# CPU.net
KiCad netlist of a schematic drawn in Altium Designer
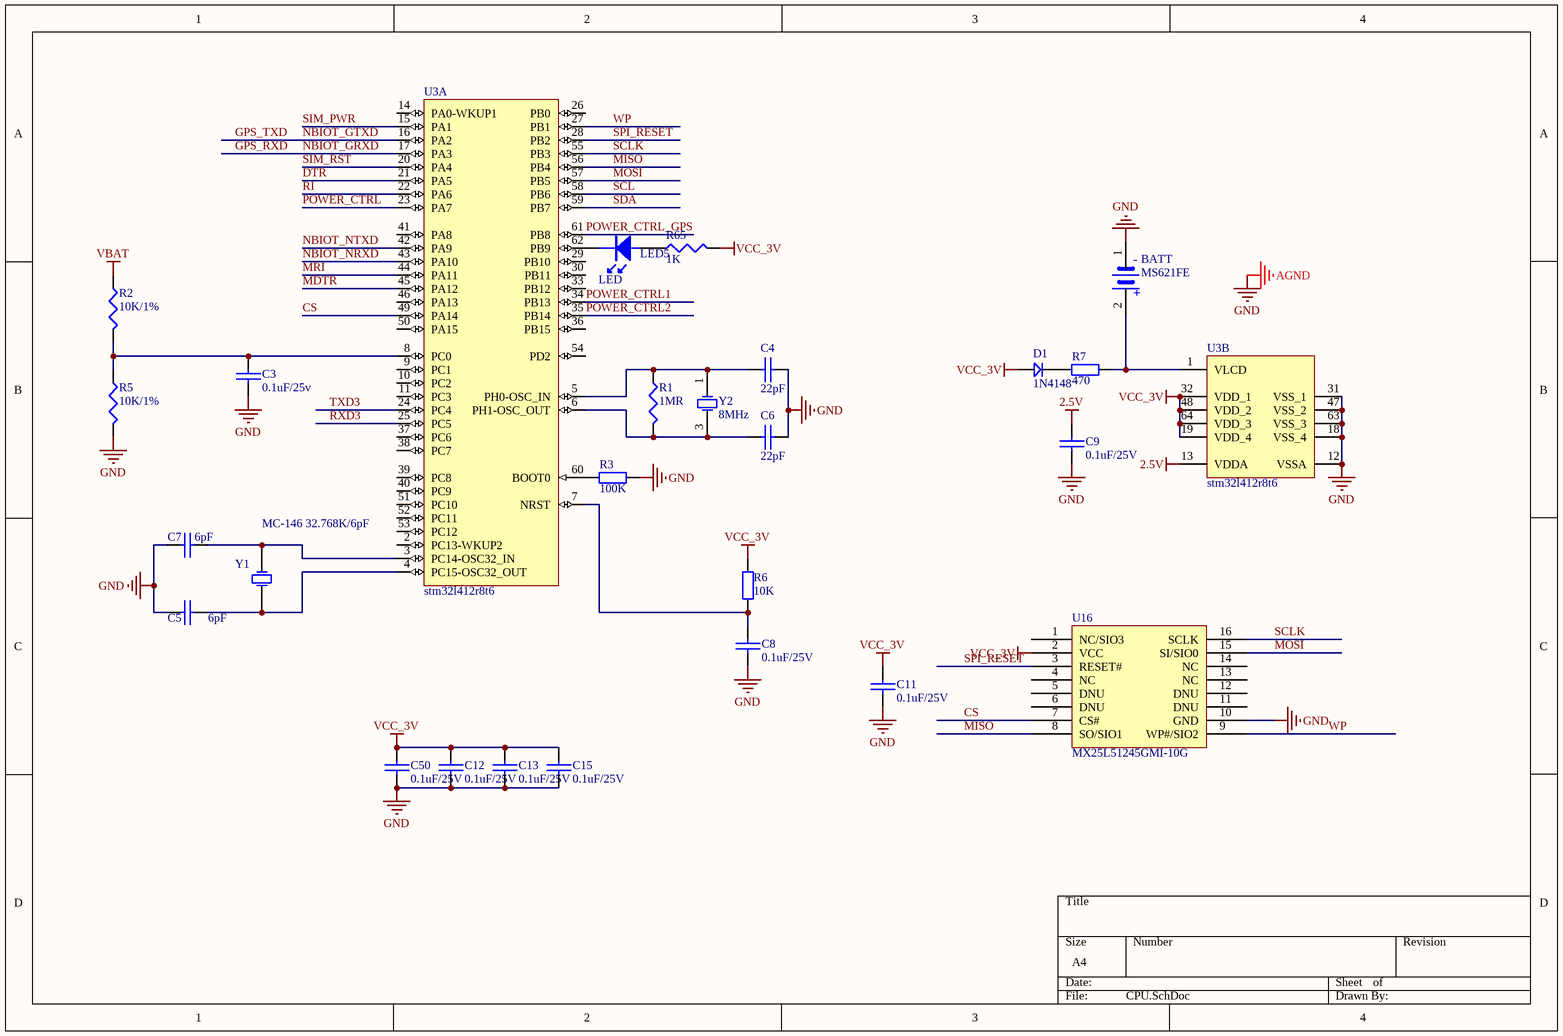
[diagram p0: CPU.SchDoc]

(export (version "E")
  (design (tool "Eeschema 10.0.6"))
  (components
    (comp (ref "BATT") (value "MS621FE") (footprint "MS621FE") (libsource (lib "Myself_1") (part "SBatery")))
    (comp (ref "C3")
      (value "0.1uF/25v")
      (footprint "0402c")
      (description "Capacitor")
      (libsource (lib "SM") (part "CAP"))
    )
    (comp (ref "C4")
      (value "22pF")
      (footprint "0402c")
      (description "Capacitor")
      (libsource (lib "SM") (part "CAP"))
    )
    (comp (ref "C5")
      (value "6pF")
      (footprint "0402c")
      (description "Capacitor")
      (libsource (lib "SM") (part "CAP"))
    )
    (comp (ref "C6")
      (value "22pF")
      (footprint "0402c")
      (description "Capacitor")
      (libsource (lib "SM") (part "CAP"))
    )
    (comp (ref "C7")
      (value "6pF")
      (footprint "0402c")
      (description "Capacitor")
      (libsource (lib "SM") (part "CAP"))
    )
    (comp (ref "C8")
      (value "0.1uF/25V")
      (footprint "0402C")
      (description "Capacitor")
      (libsource (lib "ZWLIntegrated_Library") (part "CAP"))
    )
    (comp (ref "C9")
      (value "0.1uF/25V")
      (footprint "0402C")
      (description "Capacitor")
      (libsource (lib "ZWLIntegrated_Library") (part "CAP"))
    )
    (comp (ref "C11")
      (value "0.1uF/25V")
      (footprint "0402C")
      (description "Capacitor")
      (libsource (lib "ZWLIntegrated_Library") (part "CAP"))
    )
    (comp (ref "C12")
      (value "0.1uF/25V")
      (footprint "0402C")
      (description "Capacitor")
      (libsource (lib "ZWLIntegrated_Library") (part "CAP"))
    )
    (comp (ref "C13")
      (value "0.1uF/25V")
      (footprint "0402C")
      (description "Capacitor")
      (libsource (lib "ZWLIntegrated_Library") (part "CAP"))
    )
    (comp (ref "C15")
      (value "0.1uF/25V")
      (footprint "0402C")
      (description "Capacitor")
      (libsource (lib "ZWLIntegrated_Library") (part "CAP"))
    )
    (comp (ref "C50")
      (value "0.1uF/25V")
      (footprint "0402C")
      (description "Capacitor")
      (libsource (lib "ZWLIntegrated_Library") (part "CAP"))
    )
    (comp (ref "D1")
      (value "1N4148")
      (footprint "DIODE_SOP")
      (libsource (lib "Explorer STM32F407封装库") (part "D"))
    )
    (comp (ref "LED5") (value "LED") (footprint "0603LED") (libsource (lib "我的元件库") (part "LED")))
    (comp (ref "R1")
      (value "1MR")
      (footprint "0402R")
      (description "Resistor")
      (fields (field (name "PUBLISHER") "Altium Limited"))
      (libsource (lib "SM") (part "Res3"))
    )
    (comp (ref "R2")
      (value "10K/1%")
      (footprint "0402R")
      (libsource (lib "ZWLIntegrated_Library") (part "RES1"))
    )
    (comp (ref "R3")
      (value "100K")
      (footprint "0402R")
      (description "Resistor")
      (fields (field (name "PUBLISHER") "Altium Limited"))
      (libsource (lib "Miscellaneous Devices") (part "Res2"))
    )
    (comp (ref "R5")
      (value "10K/1%")
      (footprint "0402R")
      (libsource (lib "ZWLIntegrated_Library") (part "RES1"))
    )
    (comp (ref "R6")
      (value "10K")
      (footprint "0402R")
      (description "Resistor")
      (fields (field (name "PUBLISHER") "Altium Limited"))
      (libsource (lib "") (part "Res2_1"))
    )
    (comp (ref "R7")
      (value "470")
      (footprint "0402R")
      (description "Resistor")
      (fields (field (name "PUBLISHER") "Altium Limited"))
      (libsource (lib "Miscellaneous Devices") (part "Res2"))
    )
    (comp (ref "R65")
      (value "1K")
      (footprint "0402R")
      (libsource (lib "ZWLIntegrated_Library") (part "RES1"))
    )
    (comp (ref "U3")
      (value "stm32l412r8t6")
      (footprint "LQFP-64")
      (fields (field (name "MANUFACTURER") "STMicroelectronics") (field (name "PARTNUMBER") "STM32L100R8T6"))
      (libsource (lib "STMicroelectronics STM32 L1") (part "STM32L100R8T6"))
    )
    (comp (ref "U16")
      (value "MX25L51245GMI-10G")
      (footprint "SOP127P1030X239-16N")
      (libsource (lib "stm32") (part "MX25L51245GMI-10G"))
    )
    (comp (ref "Y1")
      (value "MC-146 32.768K/6pF")
      (footprint "32.768K")
      (description "Crystal Oscillator")
      (fields (field (name "PUBLISHER") "Altium Limited"))
      (libsource (lib "") (part "XTAL_1"))
    )
    (comp (ref "Y2")
      (value "8MHz")
      (footprint "OSCILLATOR-3.2X2.5")
      (description "Crystal Oscillator")
      (fields (field (name "PUBLISHER") "Altium Limited"))
      (libsource (lib "Miscellaneous Devices") (part "XTAL"))
    )
  )
  (nets
    (net (code "1") (name "/CS") (class "Default")
      (node (ref "U16") (pin "7") (pinfunction "CS#_7") (pintype "passive"))
      (node (ref "U3") (pin "49") (pinfunction "PA14_49") (pintype "bidirectional"))
    )
    (net (code "2") (name "/DTR") (class "Default")
      (node (ref "U3") (pin "21") (pinfunction "PA5_21") (pintype "bidirectional"))
    )
    (net (code "3") (name "/GPS_RXD") (class "Default")
      (node (ref "U3") (pin "17") (pinfunction "PA3_17") (pintype "bidirectional"))
    )
    (net (code "4") (name "/GPS_TXD") (class "Default")
      (node (ref "U3") (pin "16") (pinfunction "PA2_16") (pintype "bidirectional"))
    )
    (net (code "5") (name "/MDTR") (class "Default")
      (node (ref "U3") (pin "45") (pinfunction "PA12_45") (pintype "bidirectional"))
    )
    (net (code "6") (name "/MISO") (class "Default")
      (node (ref "U16") (pin "8") (pinfunction "SO/SIO1_8") (pintype "passive"))
      (node (ref "U3") (pin "56") (pinfunction "PB4_56") (pintype "bidirectional"))
    )
    (net (code "7") (name "/MOSI") (class "Default")
      (node (ref "U16") (pin "15") (pinfunction "SI/SIO0_15") (pintype "passive"))
      (node (ref "U3") (pin "57") (pinfunction "PB5_57") (pintype "bidirectional"))
    )
    (net (code "8") (name "/MRI") (class "Default")
      (node (ref "U3") (pin "44") (pinfunction "PA11_44") (pintype "bidirectional"))
    )
    (net (code "9") (name "/NBIOT_NRXD") (class "Default")
      (node (ref "U3") (pin "43") (pinfunction "PA10_43") (pintype "bidirectional"))
    )
    (net (code "10") (name "/NBIOT_NTXD") (class "Default")
      (node (ref "U3") (pin "42") (pinfunction "PA9_42") (pintype "bidirectional"))
    )
    (net (code "11") (name "/POWER_CTRL") (class "Default")
      (node (ref "U3") (pin "23") (pinfunction "PA7_23") (pintype "bidirectional"))
    )
    (net (code "12") (name "/POWER_CTRL1") (class "Default")
      (node (ref "U3") (pin "34") (pinfunction "PB13_34") (pintype "bidirectional"))
    )
    (net (code "13") (name "/POWER_CTRL2") (class "Default")
      (node (ref "U3") (pin "35") (pinfunction "PB14_35") (pintype "bidirectional"))
    )
    (net (code "14") (name "/POWER_CTRL_GPS") (class "Default")
      (node (ref "U3") (pin "61") (pinfunction "PB8_61") (pintype "bidirectional"))
    )
    (net (code "15") (name "/RI") (class "Default")
      (node (ref "U3") (pin "22") (pinfunction "PA6_22") (pintype "bidirectional"))
    )
    (net (code "16") (name "/RXD3") (class "Default")
      (node (ref "U3") (pin "25") (pinfunction "PC5_25") (pintype "bidirectional"))
    )
    (net (code "17") (name "/SCL") (class "Default")
      (node (ref "U3") (pin "58") (pinfunction "PB6_58") (pintype "bidirectional"))
    )
    (net (code "18") (name "/SCLK") (class "Default")
      (node (ref "U16") (pin "16") (pinfunction "SCLK_16") (pintype "passive"))
      (node (ref "U3") (pin "55") (pinfunction "PB3_55") (pintype "bidirectional"))
    )
    (net (code "19") (name "/SDA") (class "Default")
      (node (ref "U3") (pin "59") (pinfunction "PB7_59") (pintype "bidirectional"))
    )
    (net (code "20") (name "/SIM_PWR") (class "Default")
      (node (ref "U3") (pin "15") (pinfunction "PA1_15") (pintype "bidirectional"))
    )
    (net (code "21") (name "/SIM_RST") (class "Default")
      (node (ref "U3") (pin "20") (pinfunction "PA4_20") (pintype "bidirectional"))
    )
    (net (code "22") (name "/SPI_RESET") (class "Default")
      (node (ref "U16") (pin "3") (pinfunction "RESET#_3") (pintype "passive"))
      (node (ref "U3") (pin "28") (pinfunction "PB2_28") (pintype "bidirectional"))
    )
    (net (code "23") (name "/TXD3") (class "Default")
      (node (ref "U3") (pin "24") (pinfunction "PC4_24") (pintype "bidirectional"))
    )
    (net (code "24") (name "/WP") (class "Default")
      (node (ref "U16") (pin "9") (pinfunction "WP#/SIO2_9") (pintype "passive"))
      (node (ref "U3") (pin "27") (pinfunction "PB1_27") (pintype "bidirectional"))
    )
    (net (code "25") (name "2.5V") (class "Default")
      (node (ref "C9") (pin "2") (pinfunction "2_2") (pintype "passive"))
      (node (ref "U3") (pin "13") (pinfunction "VDDA_13") (pintype "power_in"))
    )
    (net (code "26") (name "AGND") (class "Default")
      (node (ref "BATT") (pin "1") (pinfunction "1_1") (pintype "passive"))
      (node (ref "C11") (pin "1") (pinfunction "1_1") (pintype "passive"))
      (node (ref "C12") (pin "1") (pinfunction "1_1") (pintype "passive"))
      (node (ref "C13") (pin "1") (pinfunction "1_1") (pintype "passive"))
      (node (ref "C15") (pin "1") (pinfunction "1_1") (pintype "passive"))
      (node (ref "C3") (pin "2") (pinfunction "2_2") (pintype "passive"))
      (node (ref "C4") (pin "1") (pinfunction "1_1") (pintype "passive"))
      (node (ref "C5") (pin "2") (pinfunction "2_2") (pintype "passive"))
      (node (ref "C50") (pin "1") (pinfunction "1_1") (pintype "passive"))
      (node (ref "C6") (pin "1") (pinfunction "1_1") (pintype "passive"))
      (node (ref "C7") (pin "2") (pinfunction "2_2") (pintype "passive"))
      (node (ref "C8") (pin "1") (pinfunction "1_1") (pintype "passive"))
      (node (ref "C9") (pin "1") (pinfunction "1_1") (pintype "passive"))
      (node (ref "R3") (pin "2") (pinfunction "2_2") (pintype "passive"))
      (node (ref "R5") (pin "2") (pinfunction "2_2") (pintype "passive"))
      (node (ref "U16") (pin "10") (pinfunction "GND_10") (pintype "passive"))
      (node (ref "U3") (pin "12") (pinfunction "VSSA_12") (pintype "power_in"))
      (node (ref "U3") (pin "18") (pinfunction "VSS_4_18") (pintype "power_in"))
      (node (ref "U3") (pin "31") (pinfunction "VSS_1_31") (pintype "power_in"))
      (node (ref "U3") (pin "47") (pinfunction "VSS_2_47") (pintype "power_in"))
      (node (ref "U3") (pin "63") (pinfunction "VSS_3_63") (pintype "power_in"))
    )
    (net (code "27") (name "Net-(D1-Pad2)") (class "Default")
      (node (ref "D1") (pin "2") (pintype "passive"))
      (node (ref "R7") (pin "1") (pinfunction "1_1") (pintype "passive"))
    )
    (net (code "28") (name "Net-(LED5-Pad1)") (class "Default")
      (node (ref "LED5") (pin "1") (pinfunction "1_1") (pintype "passive"))
      (node (ref "R65") (pin "1") (pinfunction "1_1") (pintype "passive"))
    )
    (net (code "29") (name "Net-(U3A-BOOT0)") (class "Default")
      (node (ref "R3") (pin "1") (pinfunction "1_1") (pintype "passive"))
      (node (ref "U3") (pin "60") (pinfunction "BOOT0_60") (pintype "input"))
    )
    (net (code "30") (name "Net-(U3A-NRST)") (class "Default")
      (node (ref "C8") (pin "2") (pinfunction "2_2") (pintype "passive"))
      (node (ref "R6") (pin "2") (pinfunction "2_2") (pintype "passive"))
      (node (ref "U3") (pin "7") (pinfunction "NRST_7") (pintype "bidirectional"))
    )
    (net (code "31") (name "Net-(U3A-PB9)") (class "Default")
      (node (ref "LED5") (pin "2") (pinfunction "2_2") (pintype "passive"))
      (node (ref "U3") (pin "62") (pinfunction "PB9_62") (pintype "bidirectional"))
    )
    (net (code "32") (name "Net-(U3A-PC0)") (class "Default")
      (node (ref "C3") (pin "1") (pinfunction "1_1") (pintype "passive"))
      (node (ref "R2") (pin "2") (pinfunction "2_2") (pintype "passive"))
      (node (ref "R5") (pin "1") (pinfunction "1_1") (pintype "passive"))
      (node (ref "U3") (pin "8") (pinfunction "PC0_8") (pintype "bidirectional"))
    )
    (net (code "33") (name "Net-(U3A-PC14-OSC32_IN)") (class "Default")
      (node (ref "C7") (pin "1") (pinfunction "1_1") (pintype "passive"))
      (node (ref "U3") (pin "3") (pinfunction "PC14-OSC32_IN_3") (pintype "bidirectional"))
      (node (ref "Y1") (pin "1") (pinfunction "OSC1_1") (pintype "passive"))
    )
    (net (code "34") (name "Net-(U3A-PC15-OSC32_OUT)") (class "Default")
      (node (ref "C5") (pin "1") (pinfunction "1_1") (pintype "passive"))
      (node (ref "U3") (pin "4") (pinfunction "PC15-OSC32_OUT_4") (pintype "bidirectional"))
      (node (ref "Y1") (pin "2") (pinfunction "OSC2_2") (pintype "passive"))
    )
    (net (code "35") (name "Net-(U3A-PH0-OSC_IN)") (class "Default")
      (node (ref "C4") (pin "2") (pinfunction "2_2") (pintype "passive"))
      (node (ref "R1") (pin "1") (pinfunction "1_1") (pintype "passive"))
      (node (ref "U3") (pin "5") (pinfunction "PH0-OSC_IN_5") (pintype "bidirectional"))
      (node (ref "Y2") (pin "1") (pinfunction "OSC1_1") (pintype "passive"))
    )
    (net (code "36") (name "Net-(U3A-PH1-OSC_OUT)") (class "Default")
      (node (ref "C6") (pin "2") (pinfunction "2_2") (pintype "passive"))
      (node (ref "R1") (pin "2") (pinfunction "2_2") (pintype "passive"))
      (node (ref "U3") (pin "6") (pinfunction "PH1-OSC_OUT_6") (pintype "bidirectional"))
      (node (ref "Y2") (pin "3") (pinfunction "OSC2_3") (pintype "passive"))
    )
    (net (code "37") (name "Net-(U3B-VLCD)") (class "Default")
      (node (ref "BATT") (pin "2") (pinfunction "2_2") (pintype "passive"))
      (node (ref "R7") (pin "2") (pinfunction "2_2") (pintype "passive"))
      (node (ref "U3") (pin "1") (pinfunction "VLCD_1") (pintype "power_in"))
    )
    (net (code "38") (name "VBAT") (class "Default")
      (node (ref "R2") (pin "1") (pinfunction "1_1") (pintype "passive"))
    )
    (net (code "39") (name "VCC_3V") (class "Default")
      (node (ref "C11") (pin "2") (pinfunction "2_2") (pintype "passive"))
      (node (ref "C12") (pin "2") (pinfunction "2_2") (pintype "passive"))
      (node (ref "C13") (pin "2") (pinfunction "2_2") (pintype "passive"))
      (node (ref "C15") (pin "2") (pinfunction "2_2") (pintype "passive"))
      (node (ref "C50") (pin "2") (pinfunction "2_2") (pintype "passive"))
      (node (ref "D1") (pin "1") (pintype "passive"))
      (node (ref "R6") (pin "1") (pinfunction "1_1") (pintype "passive"))
      (node (ref "R65") (pin "2") (pinfunction "2_2") (pintype "passive"))
      (node (ref "U16") (pin "2") (pinfunction "VCC_2") (pintype "passive"))
      (node (ref "U3") (pin "19") (pinfunction "VDD_4_19") (pintype "power_in"))
      (node (ref "U3") (pin "32") (pinfunction "VDD_1_32") (pintype "power_in"))
      (node (ref "U3") (pin "48") (pinfunction "VDD_2_48") (pintype "power_in"))
      (node (ref "U3") (pin "64") (pinfunction "VDD_3_64") (pintype "power_in"))
    )
    (net (code "40") (name "unconnected-(U3A-PA0-WKUP1-Pad14)") (class "Default")
      (node (ref "U3") (pin "14") (pinfunction "PA0-WKUP1_14") (pintype "bidirectional"))
    )
    (net (code "41") (name "unconnected-(U3A-PA8-Pad41)") (class "Default")
      (node (ref "U3") (pin "41") (pinfunction "PA8_41") (pintype "bidirectional"))
    )
    (net (code "42") (name "unconnected-(U3A-PA13-Pad46)") (class "Default")
      (node (ref "U3") (pin "46") (pinfunction "PA13_46") (pintype "bidirectional"))
    )
    (net (code "43") (name "unconnected-(U3A-PA15-Pad50)") (class "Default")
      (node (ref "U3") (pin "50") (pinfunction "PA15_50") (pintype "bidirectional"))
    )
    (net (code "44") (name "unconnected-(U3A-PB0-Pad26)") (class "Default")
      (node (ref "U3") (pin "26") (pinfunction "PB0_26") (pintype "bidirectional"))
    )
    (net (code "45") (name "unconnected-(U3A-PB10-Pad29)") (class "Default")
      (node (ref "U3") (pin "29") (pinfunction "PB10_29") (pintype "bidirectional"))
    )
    (net (code "46") (name "unconnected-(U3A-PB11-Pad30)") (class "Default")
      (node (ref "U3") (pin "30") (pinfunction "PB11_30") (pintype "bidirectional"))
    )
    (net (code "47") (name "unconnected-(U3A-PB12-Pad33)") (class "Default")
      (node (ref "U3") (pin "33") (pinfunction "PB12_33") (pintype "bidirectional"))
    )
    (net (code "48") (name "unconnected-(U3A-PB15-Pad36)") (class "Default")
      (node (ref "U3") (pin "36") (pinfunction "PB15_36") (pintype "bidirectional"))
    )
    (net (code "49") (name "unconnected-(U3A-PC1-Pad9)") (class "Default")
      (node (ref "U3") (pin "9") (pinfunction "PC1_9") (pintype "bidirectional"))
    )
    (net (code "50") (name "unconnected-(U3A-PC2-Pad10)") (class "Default")
      (node (ref "U3") (pin "10") (pinfunction "PC2_10") (pintype "bidirectional"))
    )
    (net (code "51") (name "unconnected-(U3A-PC3-Pad11)") (class "Default")
      (node (ref "U3") (pin "11") (pinfunction "PC3_11") (pintype "bidirectional"))
    )
    (net (code "52") (name "unconnected-(U3A-PC6-Pad37)") (class "Default")
      (node (ref "U3") (pin "37") (pinfunction "PC6_37") (pintype "bidirectional"))
    )
    (net (code "53") (name "unconnected-(U3A-PC7-Pad38)") (class "Default")
      (node (ref "U3") (pin "38") (pinfunction "PC7_38") (pintype "bidirectional"))
    )
    (net (code "54") (name "unconnected-(U3A-PC8-Pad39)") (class "Default")
      (node (ref "U3") (pin "39") (pinfunction "PC8_39") (pintype "bidirectional"))
    )
    (net (code "55") (name "unconnected-(U3A-PC9-Pad40)") (class "Default")
      (node (ref "U3") (pin "40") (pinfunction "PC9_40") (pintype "bidirectional"))
    )
    (net (code "56") (name "unconnected-(U3A-PC10-Pad51)") (class "Default")
      (node (ref "U3") (pin "51") (pinfunction "PC10_51") (pintype "bidirectional"))
    )
    (net (code "57") (name "unconnected-(U3A-PC11-Pad52)") (class "Default")
      (node (ref "U3") (pin "52") (pinfunction "PC11_52") (pintype "bidirectional"))
    )
    (net (code "58") (name "unconnected-(U3A-PC12-Pad53)") (class "Default")
      (node (ref "U3") (pin "53") (pinfunction "PC12_53") (pintype "bidirectional"))
    )
    (net (code "59") (name "unconnected-(U3A-PC13-WKUP2-Pad2)") (class "Default")
      (node (ref "U3") (pin "2") (pinfunction "PC13-WKUP2_2") (pintype "bidirectional"))
    )
    (net (code "60") (name "unconnected-(U3A-PD2-Pad54)") (class "Default")
      (node (ref "U3") (pin "54") (pinfunction "PD2_54") (pintype "bidirectional"))
    )
    (net (code "61") (name "unconnected-(U16-DNU-Pad5)") (class "Default")
      (node (ref "U16") (pin "5") (pinfunction "DNU_5") (pintype "passive"))
    )
    (net (code "62") (name "unconnected-(U16-DNU-Pad6)") (class "Default")
      (node (ref "U16") (pin "6") (pinfunction "DNU_6") (pintype "passive"))
    )
    (net (code "63") (name "unconnected-(U16-DNU-Pad11)") (class "Default")
      (node (ref "U16") (pin "11") (pinfunction "DNU_11") (pintype "passive"))
    )
    (net (code "64") (name "unconnected-(U16-DNU-Pad12)") (class "Default")
      (node (ref "U16") (pin "12") (pinfunction "DNU_12") (pintype "passive"))
    )
    (net (code "65") (name "unconnected-(U16-NC-Pad4)") (class "Default")
      (node (ref "U16") (pin "4") (pinfunction "NC_4") (pintype "passive"))
    )
    (net (code "66") (name "unconnected-(U16-NC-Pad13)") (class "Default")
      (node (ref "U16") (pin "13") (pinfunction "NC_13") (pintype "passive"))
    )
    (net (code "67") (name "unconnected-(U16-NC-Pad14)") (class "Default")
      (node (ref "U16") (pin "14") (pinfunction "NC_14") (pintype "passive"))
    )
    (net (code "68") (name "unconnected-(U16-NC{slash}SIO3-Pad1)") (class "Default")
      (node (ref "U16") (pin "1") (pinfunction "NC/SIO3_1") (pintype "passive"))
    )
  )
)
